# SCH_DS3231.net
KiCad netlist of a schematic drawn in Altium Designer
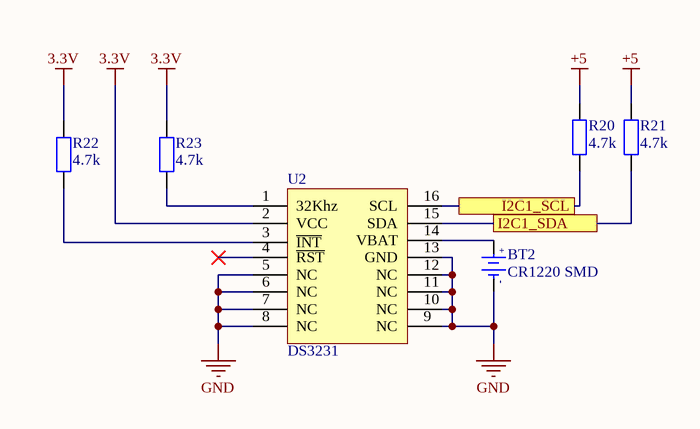
[diagram p0: SCH_DS3231.SchDoc]

(export (version "E")
  (design (tool "Eeschema 10.0.6"))
  (components
    (comp (ref "BT2")
      (value "CR1220 SMD")
      (footprint "DE PIN CR1220")
      (libsource (lib "Altium_Lib_by_KhueNguyenCreator") (part "De pin CR1220 SMD"))
    )
    (comp (ref "R20")
      (value "4.7k")
      (footprint "tro smd 0805")
      (description "Dán")
      (libsource (lib "Altium_Lib_by_KhueNguyenCreator") (part "Tro 0805 5% 4.7k"))
    )
    (comp (ref "R21")
      (value "4.7k")
      (footprint "tro smd 0805")
      (description "Dán")
      (libsource (lib "Altium_Lib_by_KhueNguyenCreator") (part "Tro 0805 5% 4.7k"))
    )
    (comp (ref "R22")
      (value "4.7k")
      (footprint "tro smd 0805")
      (description "Dán")
      (libsource (lib "Altium_Lib_by_KhueNguyenCreator") (part "Tro 0805 5% 4.7k"))
    )
    (comp (ref "R23")
      (value "4.7k")
      (footprint "tro smd 0805")
      (description "Dán")
      (libsource (lib "Altium_Lib_by_KhueNguyenCreator") (part "Tro 0805 5% 4.7k"))
    )
    (comp (ref "U2")
      (value "DS3231")
      (footprint "SOIC 16")
      (description "SOIC")
      (libsource (lib "Altium_Lib_by_KhueNguyenCreator") (part "DS3231 SMD"))
    )
  )
  (nets
    (net (code "1") (name "+5") (class "Default")
      (node (ref "R20") (pin "1") (pinfunction "1_1") (pintype "passive"))
      (node (ref "R21") (pin "2") (pinfunction "2_2") (pintype "passive"))
    )
    (net (code "2") (name "/I2C1_SCL") (class "Default")
      (node (ref "R20") (pin "2") (pinfunction "2_2") (pintype "passive"))
      (node (ref "U2") (pin "16") (pinfunction "SCL_16") (pintype "power_in"))
    )
    (net (code "3") (name "/I2C1_SDA") (class "Default")
      (node (ref "R21") (pin "1") (pinfunction "1_1") (pintype "passive"))
      (node (ref "U2") (pin "15") (pinfunction "SDA_15") (pintype "power_in"))
    )
    (net (code "4") (name "3.3V") (class "Default")
      (node (ref "R22") (pin "1") (pinfunction "1_1") (pintype "passive"))
      (node (ref "R23") (pin "2") (pinfunction "2_2") (pintype "passive"))
      (node (ref "U2") (pin "2") (pinfunction "VCC_2") (pintype "power_in"))
    )
    (net (code "5") (name "GND") (class "Default")
      (node (ref "BT2") (pin "2") (pinfunction "GND_2") (pintype "passive"))
      (node (ref "U2") (pin "10") (pinfunction "NC_10") (pintype "power_in"))
      (node (ref "U2") (pin "11") (pinfunction "NC_11") (pintype "power_in"))
      (node (ref "U2") (pin "12") (pinfunction "NC_12") (pintype "power_in"))
      (node (ref "U2") (pin "13") (pinfunction "GND_13") (pintype "power_in"))
      (node (ref "U2") (pin "5") (pinfunction "NC_5") (pintype "power_in"))
      (node (ref "U2") (pin "6") (pinfunction "NC_6") (pintype "power_in"))
      (node (ref "U2") (pin "7") (pinfunction "NC_7") (pintype "power_in"))
      (node (ref "U2") (pin "8") (pinfunction "NC_8") (pintype "power_in"))
      (node (ref "U2") (pin "9") (pinfunction "NC_9") (pintype "power_in"))
    )
    (net (code "6") (name "Net-(BT2-+3V)") (class "Default")
      (node (ref "BT2") (pin "1") (pinfunction "+3V_1") (pintype "passive"))
      (node (ref "U2") (pin "14") (pinfunction "VBAT_14") (pintype "power_in"))
    )
    (net (code "7") (name "Net-(U2-32Khz)") (class "Default")
      (node (ref "R23") (pin "1") (pinfunction "1_1") (pintype "passive"))
      (node (ref "U2") (pin "1") (pinfunction "32Khz_1") (pintype "power_in"))
    )
    (net (code "8") (name "Net-(U2-~{INT})") (class "Default")
      (node (ref "R22") (pin "2") (pinfunction "2_2") (pintype "passive"))
      (node (ref "U2") (pin "3") (pinfunction "~{INT}_3") (pintype "power_in"))
    )
    (net (code "9") (name "unconnected-(U2-~{RST}-Pad4)") (class "Default")
      (node (ref "U2") (pin "4") (pinfunction "~{RST}_4") (pintype "power_in+no_connect"))
    )
  )
)
